# cpu_core.net
KiCad netlist of a schematic drawn in Altium Designer
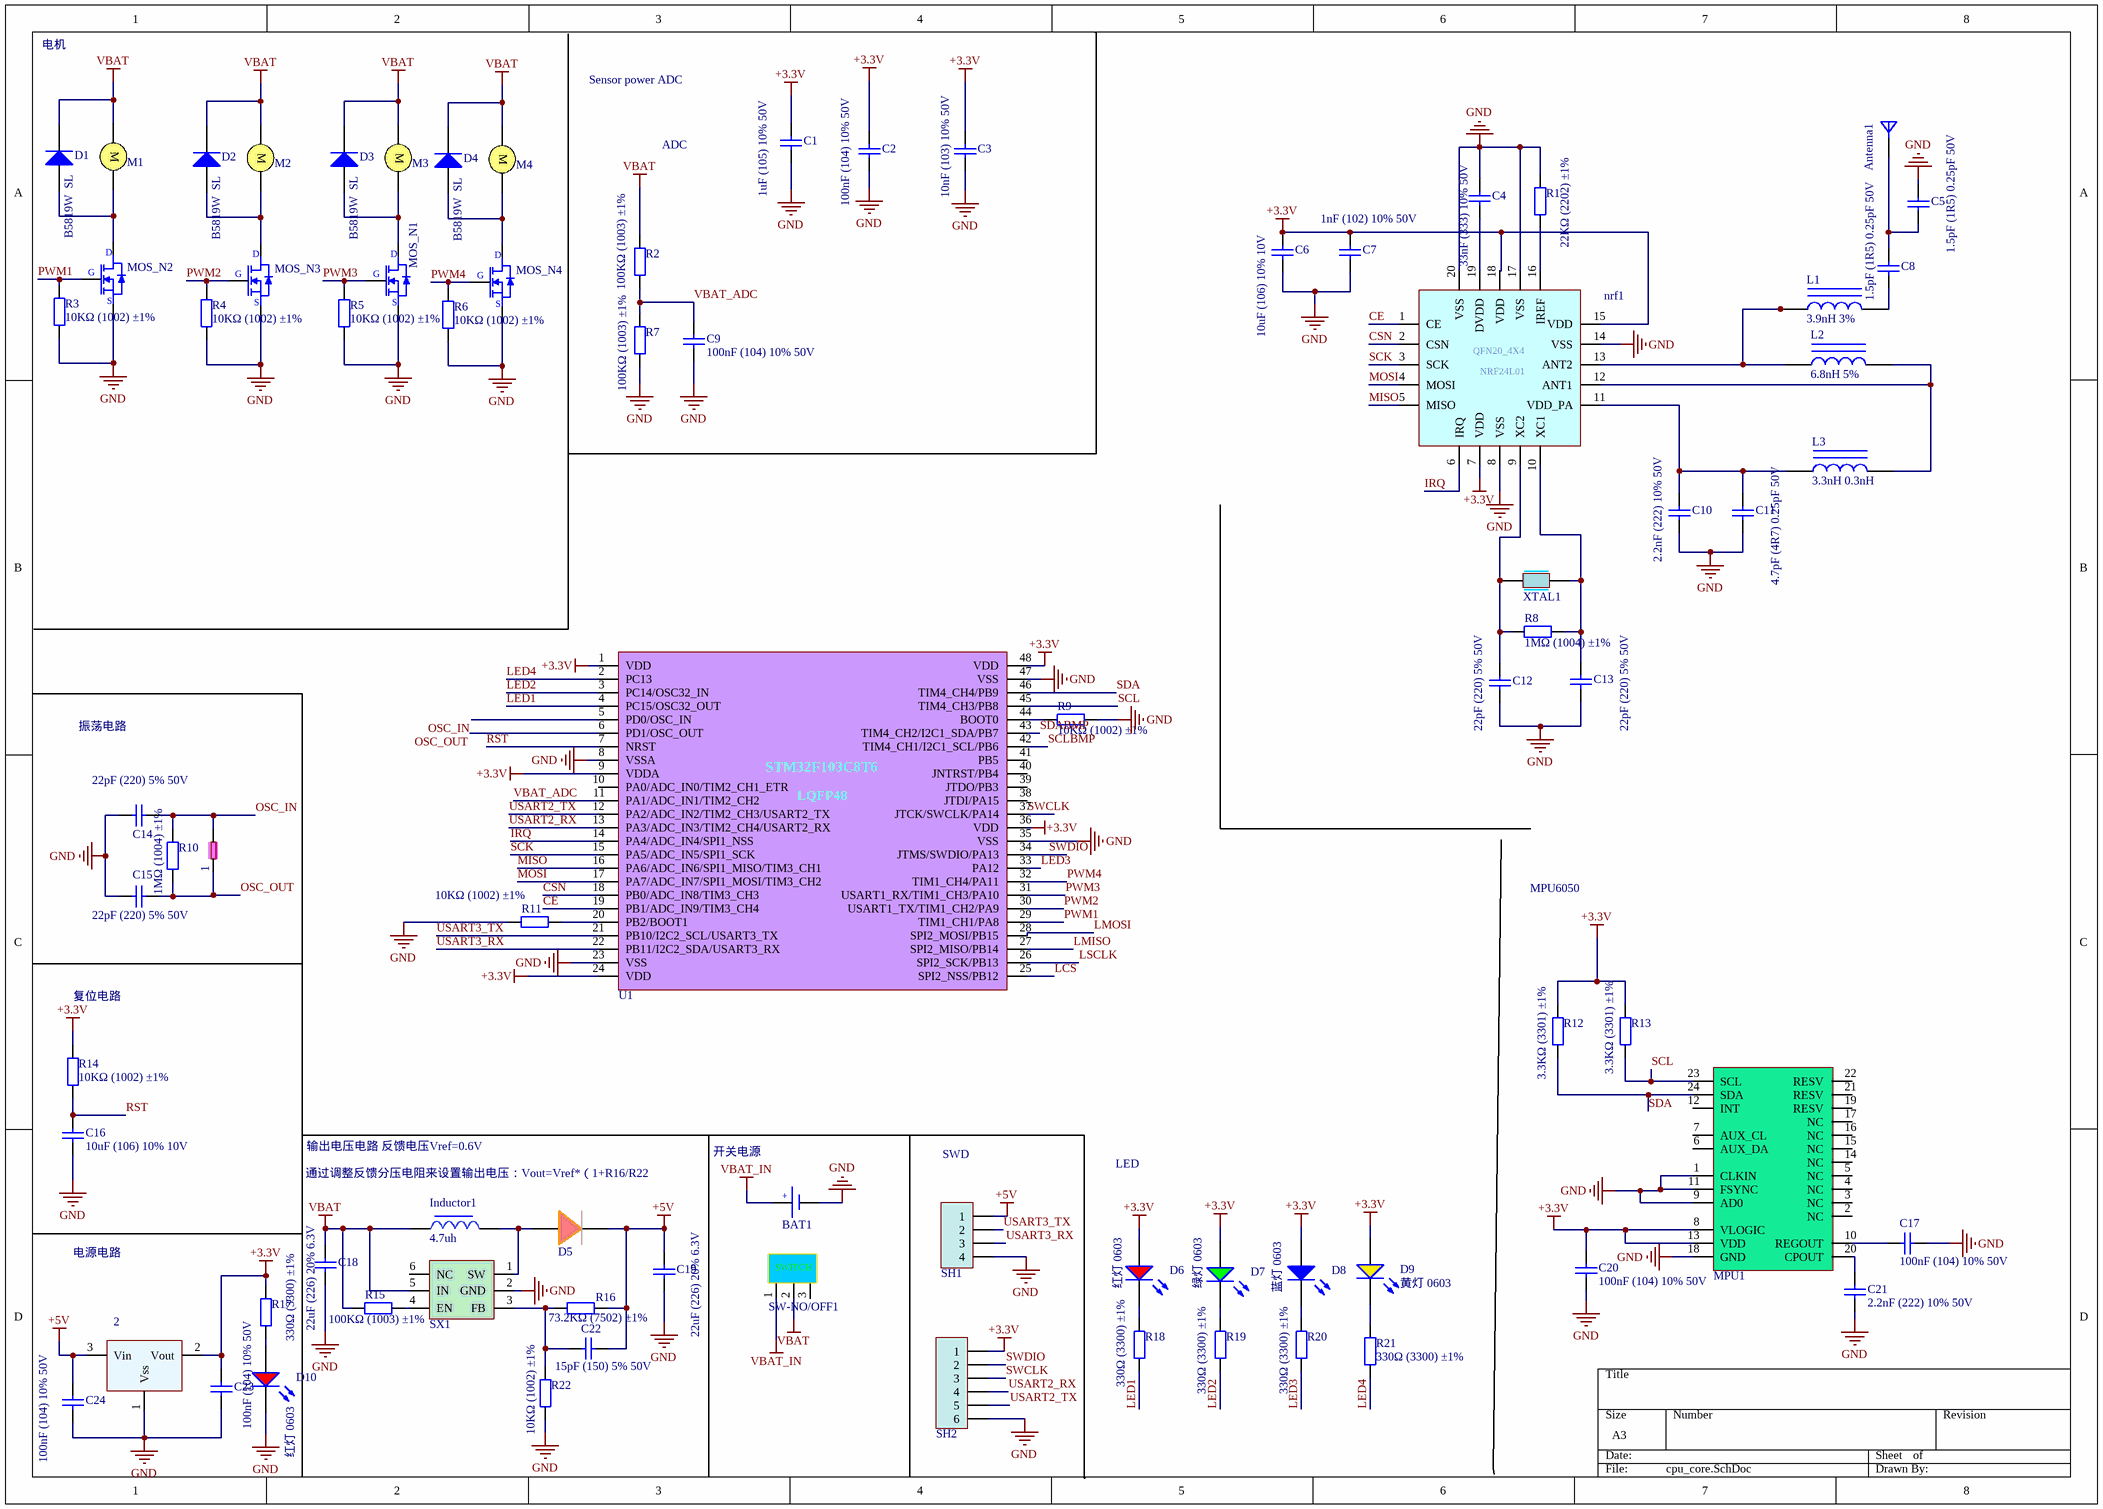
[diagram p0: cpu_core.SchDoc]

(export (version "E")
  (design (tool "Eeschema 10.0.6"))
  (components
    (comp (ref "1")
      (value "5032-8MHZ")
      (footprint "5032-8MHZ")
      (libsource (lib "self_schlib v1.8.6") (part "5032-8MHZ"))
    )
    (comp (ref "2")
      (value "662K-3.3V(SOT-23-3)")
      (footprint "SOT-23-3")
      (libsource (lib "self_schlib v1.8.6") (part "662K-3.3V(SOT-23-3)"))
    )
    (comp (ref "Antenna1")
      (value "Antenna")
      (footprint "Antenna")
      (libsource (lib "self_schlib v1.8.6") (part "Antenna"))
    )
    (comp (ref "BAT1") (value "BAT") (footprint "BAT") (libsource (lib "self_schlib v1.8.6") (part "BAT")))
    (comp (ref "C1")
      (value "1uF (105) 10% 50V")
      (footprint "0603_C")
      (description "贴片电容")
      (libsource (lib "Miscellaneous Devices Legend") (part "0603 1uF (105) 10% 50V"))
    )
    (comp (ref "C2")
      (value "100nF (104) 10% 50V")
      (footprint "0603_C")
      (description "贴片电容")
      (libsource (lib "Miscellaneous Devices Legend") (part "0603 100nF (104) 10% 50V"))
    )
    (comp (ref "C3")
      (value "10nF (103) 10% 50V")
      (footprint "0603_C")
      (description "贴片电容")
      (libsource (lib "Miscellaneous Devices Legend") (part "0603 10nF (103) 10% 50V"))
    )
    (comp (ref "C4")
      (value "33nF (333) 10% 50V")
      (footprint "0603_C")
      (description "贴片电容")
      (libsource (lib "Miscellaneous Devices Legend") (part "0603 33nF (333) 10% 50V"))
    )
    (comp (ref "C5")
      (value "1.5pF (1R5) 0.25pF 50V")
      (footprint "0402_C")
      (description "贴片电容")
      (libsource (lib "Miscellaneous Devices Legend") (part "0402 1.5pF (1R5) 0.25pF 50V"))
    )
    (comp (ref "C6")
      (value "10uF (106) 10% 10V")
      (footprint "0603_C")
      (description "贴片电容")
      (libsource (lib "Miscellaneous Devices Legend") (part "0603 10uF (106) 10% 10V"))
    )
    (comp (ref "C7")
      (value "1nF (102) 10% 50V")
      (footprint "0603_C")
      (description "贴片电容")
      (libsource (lib "Miscellaneous Devices Legend") (part "0603 1nF (102) 10% 50V"))
    )
    (comp (ref "C8")
      (value "1.5pF (1R5) 0.25pF 50V")
      (footprint "0402_C")
      (description "贴片电容")
      (libsource (lib "Miscellaneous Devices Legend") (part "0402 1.5pF (1R5) 0.25pF 50V"))
    )
    (comp (ref "C9")
      (value "100nF (104) 10% 50V")
      (footprint "0603_C")
      (description "贴片电容")
      (libsource (lib "Miscellaneous Devices Legend") (part "0603 100nF (104) 10% 50V"))
    )
    (comp (ref "C10")
      (value "2.2nF (222) 10% 50V")
      (footprint "0603_C")
      (description "贴片电容")
      (libsource (lib "Miscellaneous Devices Legend") (part "0603 2.2nF (222) 10% 50V"))
    )
    (comp (ref "C11")
      (value "4.7pF (4R7) 0.25pF 50V")
      (footprint "0603_C")
      (description "贴片电容")
      (libsource (lib "Miscellaneous Devices Legend") (part "0603 4.7pF (4R7) 0.25pF 50V"))
    )
    (comp (ref "C12")
      (value "22pF (220) 5% 50V")
      (footprint "0603_C")
      (description "贴片电容")
      (libsource (lib "Miscellaneous Devices Legend") (part "0603 22pF (220) 5% 50V"))
    )
    (comp (ref "C13")
      (value "22pF (220) 5% 50V")
      (footprint "0603_C")
      (description "贴片电容")
      (libsource (lib "Miscellaneous Devices Legend") (part "0603 22pF (220) 5% 50V"))
    )
    (comp (ref "C14")
      (value "22pF (220) 5% 50V")
      (footprint "0603_C")
      (description "贴片电容")
      (libsource (lib "Miscellaneous Devices Legend") (part "0603 22pF (220) 5% 50V"))
    )
    (comp (ref "C15")
      (value "22pF (220) 5% 50V")
      (footprint "0603_C")
      (description "贴片电容")
      (libsource (lib "Miscellaneous Devices Legend") (part "0603 22pF (220) 5% 50V"))
    )
    (comp (ref "C16")
      (value "10uF (106) 10% 10V")
      (footprint "0603_C")
      (description "贴片电容")
      (libsource (lib "Miscellaneous Devices Legend") (part "0603 10uF (106) 10% 10V"))
    )
    (comp (ref "C17")
      (value "100nF (104) 10% 50V")
      (footprint "0603_C")
      (description "贴片电容")
      (libsource (lib "Miscellaneous Devices Legend") (part "0603 100nF (104) 10% 50V"))
    )
    (comp (ref "C18")
      (value "22uF (226) 20% 6.3V")
      (footprint "0603_C")
      (description "贴片电容")
      (libsource (lib "Miscellaneous Devices Legend") (part "0603 22uF (226) 20% 6.3V"))
    )
    (comp (ref "C19")
      (value "22uF (226) 20% 6.3V")
      (footprint "0603_C")
      (description "贴片电容")
      (libsource (lib "Miscellaneous Devices Legend") (part "0603 22uF (226) 20% 6.3V"))
    )
    (comp (ref "C20")
      (value "100nF (104) 10% 50V")
      (footprint "0603_C")
      (description "贴片电容")
      (libsource (lib "Miscellaneous Devices Legend") (part "0603 100nF (104) 10% 50V"))
    )
    (comp (ref "C21")
      (value "2.2nF (222) 10% 50V")
      (footprint "0603_C")
      (description "贴片电容")
      (libsource (lib "Miscellaneous Devices Legend") (part "0603 2.2nF (222) 10% 50V"))
    )
    (comp (ref "C22")
      (value "15pF (150) 5% 50V")
      (footprint "0603_C")
      (description "贴片电容")
      (libsource (lib "Miscellaneous Devices Legend") (part "0603 15pF (150) 5% 50V"))
    )
    (comp (ref "C23")
      (value "100nF (104) 10% 50V")
      (footprint "0603_C")
      (description "贴片电容")
      (libsource (lib "Miscellaneous Devices Legend") (part "0603 100nF (104) 10% 50V"))
    )
    (comp (ref "C24")
      (value "100nF (104) 10% 50V")
      (footprint "0603_C")
      (description "贴片电容")
      (libsource (lib "Miscellaneous Devices Legend") (part "0603 100nF (104) 10% 50V"))
    )
    (comp (ref "D1")
      (value "B5819W  SL")
      (footprint "SOD-123")
      (description "肖特基二极管")
      (libsource (lib "Miscellaneous Devices Legend") (part "SOD-123 B5819W  SL"))
    )
    (comp (ref "D2")
      (value "B5819W  SL")
      (footprint "SOD-123")
      (description "肖特基二极管")
      (libsource (lib "Miscellaneous Devices Legend") (part "SOD-123 B5819W  SL"))
    )
    (comp (ref "D3")
      (value "B5819W  SL")
      (footprint "SOD-123")
      (description "肖特基二极管")
      (libsource (lib "Miscellaneous Devices Legend") (part "SOD-123 B5819W  SL"))
    )
    (comp (ref "D4")
      (value "B5819W  SL")
      (footprint "SOD-123")
      (description "肖特基二极管")
      (libsource (lib "Miscellaneous Devices Legend") (part "SOD-123 B5819W  SL"))
    )
    (comp (ref "D5")
      (value "SMA/DO-214")
      (footprint "SMA/DO-214")
      (libsource (lib "self_schlib v1.8.6") (part "SMA/DO-214"))
    )
    (comp (ref "D6")
      (value "红灯 0603")
      (footprint "0603_LED_S1")
      (description "发光二极管")
      (libsource (lib "Miscellaneous Devices Legend") (part "0603 红灯"))
    )
    (comp (ref "D7")
      (value "绿灯 0603")
      (footprint "0603_LED_S1")
      (description "发光二极管")
      (libsource (lib "Miscellaneous Devices Legend") (part "0603 绿灯"))
    )
    (comp (ref "D8")
      (value "蓝灯 0603")
      (footprint "0603_LED_S1")
      (description "发光二极管")
      (libsource (lib "Miscellaneous Devices Legend") (part "0603 蓝灯"))
    )
    (comp (ref "D9")
      (value "黄灯 0603")
      (footprint "0603_LED_S1")
      (description "发光二极管")
      (libsource (lib "Miscellaneous Devices Legend") (part "0603 黄灯"))
    )
    (comp (ref "D10")
      (value "红灯 0603")
      (footprint "0603_LED_S1")
      (description "发光二极管")
      (libsource (lib "Miscellaneous Devices Legend") (part "0603 红灯"))
    )
    (comp (ref "Inductor1")
      (value "Inductor")
      (footprint "CD32")
      (fields (field (name "ALTIUM_UNNAMED_1") "4.7uh"))
      (libsource (lib "self_schlib v1.8.6") (part "Inductor"))
    )
    (comp (ref "L1")
      (value "3.9nH 3%")
      (footprint "0402_L")
      (description "贴片电感")
      (libsource (lib "Miscellaneous Devices Legend") (part "0402 3.9nH 3%"))
    )
    (comp (ref "L2")
      (value "6.8nH 5%")
      (footprint "0402_L")
      (description "贴片电感")
      (libsource (lib "Miscellaneous Devices Legend") (part "0402 6.8nH 5%"))
    )
    (comp (ref "L3")
      (value "3.3nH 0.3nH")
      (footprint "0402_L")
      (description "贴片电感")
      (libsource (lib "Miscellaneous Devices Legend") (part "0402 3.3nH 0.3nH"))
    )
    (comp (ref "M1") (value "MOTO") (footprint "MOTO") (libsource (lib "self_schlib v1.8.6") (part "MOTO")))
    (comp (ref "M2") (value "MOTO") (footprint "MOTO") (libsource (lib "self_schlib v1.8.6") (part "MOTO")))
    (comp (ref "M3") (value "MOTO") (footprint "MOTO") (libsource (lib "self_schlib v1.8.6") (part "MOTO")))
    (comp (ref "M4") (value "MOTO") (footprint "MOTO") (libsource (lib "self_schlib v1.8.6") (part "MOTO")))
    (comp (ref "MOS_N1")
      (value "MOS_N")
      (footprint "SOT-23-3")
      (libsource (lib "self_schlib v1.8.6") (part "MOS_N_(SOT-23-3)"))
    )
    (comp (ref "MOS_N2")
      (value "MOS_N")
      (footprint "SOT-23-3")
      (libsource (lib "self_schlib v1.8.6") (part "MOS_N_(SOT-23-3)"))
    )
    (comp (ref "MOS_N3")
      (value "MOS_N")
      (footprint "SOT-23-3")
      (libsource (lib "self_schlib v1.8.6") (part "MOS_N_(SOT-23-3)"))
    )
    (comp (ref "MOS_N4")
      (value "MOS_N")
      (footprint "SOT-23-3")
      (libsource (lib "self_schlib v1.8.6") (part "MOS_N_(SOT-23-3)"))
    )
    (comp (ref "MPU1")
      (value "MPU6050")
      (footprint "QFN24_4X4")
      (libsource (lib "self_schlib v1.8.6") (part "MPU6050(QFN24_4X4)"))
    )
    (comp (ref "nrf1")
      (value "nrf24l01")
      (footprint "QFN20_4X4")
      (libsource (lib "self_schlib v1.8.6") (part "QFN20-4X4"))
    )
    (comp (ref "R1")
      (value "22KΩ (2202) ±1%")
      (footprint "0603_R")
      (description "贴片电阻")
      (libsource (lib "Miscellaneous Devices Legend") (part "0603 22KΩ (2202) 1%"))
    )
    (comp (ref "R2")
      (value "100KΩ (1003) ±1%")
      (footprint "0603_R")
      (description "贴片电阻")
      (libsource (lib "") (part "0603 100KΩ (1003) 1%_1"))
    )
    (comp (ref "R3")
      (value "10KΩ (1002) ±1%")
      (footprint "0603_R")
      (description "贴片电阻")
      (libsource (lib "Miscellaneous Devices Legend") (part "0603 10KΩ (1002) 1%"))
    )
    (comp (ref "R4")
      (value "10KΩ (1002) ±1%")
      (footprint "0603_R")
      (description "贴片电阻")
      (libsource (lib "Miscellaneous Devices Legend") (part "0603 10KΩ (1002) 1%"))
    )
    (comp (ref "R5")
      (value "10KΩ (1002) ±1%")
      (footprint "0603_R")
      (description "贴片电阻")
      (libsource (lib "Miscellaneous Devices Legend") (part "0603 10KΩ (1002) 1%"))
    )
    (comp (ref "R6")
      (value "10KΩ (1002) ±1%")
      (footprint "0603_R")
      (description "贴片电阻")
      (libsource (lib "Miscellaneous Devices Legend") (part "0603 10KΩ (1002) 1%"))
    )
    (comp (ref "R7")
      (value "100KΩ (1003) ±1%")
      (footprint "0603_R")
      (description "贴片电阻")
      (libsource (lib "") (part "0603 100KΩ (1003) 1%_1"))
    )
    (comp (ref "R8")
      (value "1MΩ (1004) ±1%")
      (footprint "0603_R")
      (description "贴片电阻")
      (libsource (lib "Miscellaneous Devices Legend") (part "0603 1MΩ (1004) 1%"))
    )
    (comp (ref "R9")
      (value "10KΩ (1002) ±1%")
      (footprint "0603_R")
      (description "贴片电阻")
      (libsource (lib "") (part "0603 10KΩ (1002) 1%_1"))
    )
    (comp (ref "R10")
      (value "1MΩ (1004) ±1%")
      (footprint "0603_R")
      (description "贴片电阻")
      (libsource (lib "") (part "0603 1MΩ (1004) 1%_1"))
    )
    (comp (ref "R11")
      (value "10KΩ (1002) ±1%")
      (footprint "0603_R")
      (description "贴片电阻")
      (libsource (lib "") (part "0603 10KΩ (1002) 1%_2"))
    )
    (comp (ref "R12")
      (value "3.3KΩ (3301) ±1%")
      (footprint "0603_R")
      (description "贴片电阻")
      (libsource (lib "Miscellaneous Devices Legend") (part "0603 3.3KΩ (3301) 1%"))
    )
    (comp (ref "R13")
      (value "3.3KΩ (3301) ±1%")
      (footprint "0603_R")
      (description "贴片电阻")
      (libsource (lib "Miscellaneous Devices Legend") (part "0603 3.3KΩ (3301) 1%"))
    )
    (comp (ref "R14")
      (value "10KΩ (1002) ±1%")
      (footprint "0603_R")
      (description "贴片电阻")
      (libsource (lib "Miscellaneous Devices Legend") (part "0603 10KΩ (1002) 1%"))
    )
    (comp (ref "R15")
      (value "100KΩ (1003) ±1%")
      (footprint "0603_R")
      (description "贴片电阻")
      (libsource (lib "Miscellaneous Devices Legend") (part "0603 100KΩ (1003) 1%"))
    )
    (comp (ref "R16")
      (value "73.2KΩ (7502) ±1%")
      (footprint "0603_R")
      (description "贴片电阻")
      (libsource (lib "Miscellaneous Devices Legend") (part "0603 75KΩ (7502) 1%"))
    )
    (comp (ref "R17")
      (value "330Ω (3300) ±1%")
      (footprint "0603_R")
      (description "贴片电阻")
      (libsource (lib "Miscellaneous Devices Legend") (part "0603 330Ω (3300) 1%"))
    )
    (comp (ref "R18")
      (value "330Ω (3300) ±1%")
      (footprint "0603_R")
      (description "贴片电阻")
      (libsource (lib "Miscellaneous Devices Legend") (part "0603 330Ω (3300) 1%"))
    )
    (comp (ref "R19")
      (value "330Ω (3300) ±1%")
      (footprint "0603_R")
      (description "贴片电阻")
      (libsource (lib "Miscellaneous Devices Legend") (part "0603 330Ω (3300) 1%"))
    )
    (comp (ref "R20")
      (value "330Ω (3300) ±1%")
      (footprint "0603_R")
      (description "贴片电阻")
      (libsource (lib "Miscellaneous Devices Legend") (part "0603 330Ω (3300) 1%"))
    )
    (comp (ref "R21")
      (value "330Ω (3300) ±1%")
      (footprint "0603_R")
      (description "贴片电阻")
      (libsource (lib "Miscellaneous Devices Legend") (part "0603 330Ω (3300) 1%"))
    )
    (comp (ref "R22")
      (value "10KΩ (1002) ±1%")
      (footprint "0603_R")
      (description "贴片电阻")
      (libsource (lib "Miscellaneous Devices Legend") (part "0603 10KΩ (1002) 1%"))
    )
    (comp (ref "SH1")
      (value "SH1.0mm-4PIN")
      (footprint "SH1.0mm-4PIN")
      (libsource (lib "self_schlib v1.8.6") (part "SH1.0mm-4PIN"))
    )
    (comp (ref "SH2")
      (value "SH1.0mm-6PIN")
      (footprint "SH1.0mm-6PIN")
      (libsource (lib "self_schlib v1.8.6") (part "SH1.0mm-6PIN"))
    )
    (comp (ref "SW-NO/OFF1")
      (value "SW-NO/OFF")
      (footprint "SW-NO/OFF-PIN3")
      (libsource (lib "self_schlib v1.8.6") (part "SW-NO/OFF-PIN3"))
    )
    (comp (ref "SX1")
      (value "SX1308")
      (footprint "SX1308")
      (libsource (lib "self_schlib v1.8.6") (part "SX1308"))
    )
    (comp (ref "U1")
      (value "STM32F103C8T6")
      (footprint "STM32F103C8T6")
      (libsource (lib "self_schlib v1.8.6") (part "STM32F103C8T6"))
    )
    (comp (ref "XTAL1")
      (value "Crystal Oscillator 3225")
      (footprint "Crystal Oscillator 3225")
      (libsource (lib "self_schlib v1.8.6") (part "Crystal Oscillator 3225"))
    )
  )
  (nets
    (net (code "1") (name "+3.3V") (class "Default")
      (node (ref "2") (pin "2") (pinfunction "Vout_2") (pintype "passive"))
      (node (ref "C1") (pin "2") (pinfunction "2_2") (pintype "passive"))
      (node (ref "C2") (pin "2") (pinfunction "2_2") (pintype "passive"))
      (node (ref "C20") (pin "2") (pinfunction "2_2") (pintype "passive"))
      (node (ref "C23") (pin "2") (pinfunction "2_2") (pintype "passive"))
      (node (ref "C3") (pin "2") (pinfunction "2_2") (pintype "passive"))
      (node (ref "C6") (pin "2") (pinfunction "2_2") (pintype "passive"))
      (node (ref "C7") (pin "2") (pinfunction "2_2") (pintype "passive"))
      (node (ref "D6") (pin "A") (pinfunction "A_A") (pintype "passive"))
      (node (ref "D7") (pin "A") (pinfunction "A_A") (pintype "passive"))
      (node (ref "D8") (pin "A") (pinfunction "A_A") (pintype "passive"))
      (node (ref "D9") (pin "A") (pinfunction "A_A") (pintype "passive"))
      (node (ref "MPU1") (pin "13") (pinfunction "VDD_13") (pintype "passive"))
      (node (ref "MPU1") (pin "8") (pinfunction "VLOGIC_8") (pintype "passive"))
      (node (ref "R12") (pin "2") (pinfunction "2_2") (pintype "passive"))
      (node (ref "R13") (pin "2") (pinfunction "2_2") (pintype "passive"))
      (node (ref "R14") (pin "2") (pinfunction "2_2") (pintype "passive"))
      (node (ref "R17") (pin "2") (pinfunction "2_2") (pintype "passive"))
      (node (ref "SH2") (pin "1") (pinfunction "1_1") (pintype "passive"))
      (node (ref "U1") (pin "1") (pinfunction "VDD_1") (pintype "passive"))
      (node (ref "U1") (pin "24") (pinfunction "VDD_24") (pintype "passive"))
      (node (ref "U1") (pin "36") (pinfunction "VDD_36") (pintype "passive"))
      (node (ref "U1") (pin "48") (pinfunction "VDD_48") (pintype "passive"))
      (node (ref "U1") (pin "9") (pinfunction "VDDA_9") (pintype "passive"))
      (node (ref "nrf1") (pin "15") (pinfunction "VDD_15") (pintype "passive"))
      (node (ref "nrf1") (pin "7") (pinfunction "VDD_7") (pintype "passive"))
    )
    (net (code "2") (name "+5V") (class "Default")
      (node (ref "2") (pin "3") (pinfunction "Vin_3") (pintype "passive"))
      (node (ref "C19") (pin "2") (pinfunction "2_2") (pintype "passive"))
      (node (ref "C22") (pin "2") (pinfunction "2_2") (pintype "passive"))
      (node (ref "C24") (pin "2") (pinfunction "2_2") (pintype "passive"))
      (node (ref "D5") (pin "2") (pinfunction "2_2") (pintype "passive"))
      (node (ref "R16") (pin "2") (pinfunction "2_2") (pintype "passive"))
      (node (ref "SH1") (pin "1") (pinfunction "1_1") (pintype "passive"))
    )
    (net (code "3") (name "/CE") (class "Default")
      (node (ref "U1") (pin "19") (pinfunction "PB1/ADC_IN9/TIM3_CH4_19") (pintype "passive"))
      (node (ref "nrf1") (pin "1") (pinfunction "CE_1") (pintype "passive"))
    )
    (net (code "4") (name "/CSN") (class "Default")
      (node (ref "U1") (pin "18") (pinfunction "PB0/ADC_IN8/TIM3_CH3_18") (pintype "passive"))
      (node (ref "nrf1") (pin "2") (pinfunction "CSN_2") (pintype "passive"))
    )
    (net (code "5") (name "/IRQ") (class "Default")
      (node (ref "U1") (pin "14") (pinfunction "PA4/ADC_IN4/SPI1_NSS_14") (pintype "passive"))
      (node (ref "nrf1") (pin "6") (pinfunction "IRQ_6") (pintype "passive"))
    )
    (net (code "6") (name "/LCS") (class "Default")
      (node (ref "U1") (pin "25") (pinfunction "SPI2_NSS/PB12_25") (pintype "passive"))
    )
    (net (code "7") (name "/LED1") (class "Default")
      (node (ref "R18") (pin "1") (pinfunction "1_1") (pintype "passive"))
      (node (ref "U1") (pin "4") (pinfunction "PC15/OSC32_OUT_4") (pintype "passive"))
    )
    (net (code "8") (name "/LED2") (class "Default")
      (node (ref "R19") (pin "1") (pinfunction "1_1") (pintype "passive"))
      (node (ref "U1") (pin "3") (pinfunction "PC14/OSC32_IN_3") (pintype "passive"))
    )
    (net (code "9") (name "/LED3") (class "Default")
      (node (ref "R20") (pin "1") (pinfunction "1_1") (pintype "passive"))
      (node (ref "U1") (pin "33") (pinfunction "PA12_33") (pintype "passive"))
    )
    (net (code "10") (name "/LED4") (class "Default")
      (node (ref "R21") (pin "1") (pinfunction "1_1") (pintype "passive"))
      (node (ref "U1") (pin "2") (pinfunction "PC13_2") (pintype "passive"))
    )
    (net (code "11") (name "/LMISO") (class "Default")
      (node (ref "U1") (pin "27") (pinfunction "SPI2_MISO/PB14_27") (pintype "passive"))
    )
    (net (code "12") (name "/LMOSI") (class "Default")
      (node (ref "U1") (pin "28") (pinfunction "SPI2_MOSI/PB15_28") (pintype "passive"))
    )
    (net (code "13") (name "/LSCLK") (class "Default")
      (node (ref "U1") (pin "26") (pinfunction "SPI2_SCK/PB13_26") (pintype "passive"))
    )
    (net (code "14") (name "/MISO") (class "Default")
      (node (ref "U1") (pin "16") (pinfunction "PA6/ADC_IN6/SPI1_MISO/TIM3_CH1_16") (pintype "passive"))
      (node (ref "nrf1") (pin "5") (pinfunction "MISO_5") (pintype "passive"))
    )
    (net (code "15") (name "/MOSI") (class "Default")
      (node (ref "U1") (pin "17") (pinfunction "PA7/ADC_IN7/SPI1_MOSI/TIM3_CH2_17") (pintype "passive"))
      (node (ref "nrf1") (pin "4") (pinfunction "MOSI_4") (pintype "passive"))
    )
    (net (code "16") (name "/OSC_IN") (class "Default")
      (node (ref "1") (pin "3") (pinfunction "3_3") (pintype "passive"))
      (node (ref "C14") (pin "2") (pinfunction "2_2") (pintype "passive"))
      (node (ref "R10") (pin "2") (pinfunction "2_2") (pintype "passive"))
      (node (ref "U1") (pin "5") (pinfunction "PD0/OSC_IN_5") (pintype "passive"))
    )
    (net (code "17") (name "/OSC_OUT") (class "Default")
      (node (ref "1") (pin "1") (pinfunction "1_1") (pintype "passive"))
      (node (ref "C15") (pin "2") (pinfunction "2_2") (pintype "passive"))
      (node (ref "R10") (pin "1") (pinfunction "1_1") (pintype "passive"))
      (node (ref "U1") (pin "6") (pinfunction "PD1/OSC_OUT_6") (pintype "passive"))
    )
    (net (code "18") (name "/PWM1") (class "Default")
      (node (ref "MOS_N2") (pin "1") (pinfunction "G_1") (pintype "passive"))
      (node (ref "R3") (pin "2") (pinfunction "2_2") (pintype "passive"))
      (node (ref "U1") (pin "29") (pinfunction "TIM1_CH1/PA8_29") (pintype "passive"))
    )
    (net (code "19") (name "/PWM2") (class "Default")
      (node (ref "MOS_N3") (pin "1") (pinfunction "G_1") (pintype "passive"))
      (node (ref "R4") (pin "2") (pinfunction "2_2") (pintype "passive"))
      (node (ref "U1") (pin "30") (pinfunction "USART1_TX/TIM1_CH2/PA9_30") (pintype "passive"))
    )
    (net (code "20") (name "/PWM3") (class "Default")
      (node (ref "MOS_N1") (pin "1") (pinfunction "G_1") (pintype "passive"))
      (node (ref "R5") (pin "2") (pinfunction "2_2") (pintype "passive"))
      (node (ref "U1") (pin "31") (pinfunction "USART1_RX/TIM1_CH3/PA10_31") (pintype "passive"))
    )
    (net (code "21") (name "/PWM4") (class "Default")
      (node (ref "MOS_N4") (pin "1") (pinfunction "G_1") (pintype "passive"))
      (node (ref "R6") (pin "2") (pinfunction "2_2") (pintype "passive"))
      (node (ref "U1") (pin "32") (pinfunction "TIM1_CH4/PA11_32") (pintype "passive"))
    )
    (net (code "22") (name "/RST") (class "Default")
      (node (ref "C16") (pin "2") (pinfunction "2_2") (pintype "passive"))
      (node (ref "R14") (pin "1") (pinfunction "1_1") (pintype "passive"))
      (node (ref "U1") (pin "7") (pinfunction "NRST_7") (pintype "passive"))
    )
    (net (code "23") (name "/SCK") (class "Default")
      (node (ref "U1") (pin "15") (pinfunction "PA5/ADC_IN5/SPI1_SCK_15") (pintype "passive"))
      (node (ref "nrf1") (pin "3") (pinfunction "SCK_3") (pintype "passive"))
    )
    (net (code "24") (name "/SCL") (class "Default")
      (node (ref "MPU1") (pin "23") (pinfunction "SCL_23") (pintype "passive"))
      (node (ref "R13") (pin "1") (pinfunction "1_1") (pintype "passive"))
      (node (ref "U1") (pin "45") (pinfunction "TIM4_CH3/PB8_45") (pintype "passive"))
    )
    (net (code "25") (name "/SCLBMP") (class "Default")
      (node (ref "U1") (pin "42") (pinfunction "TIM4_CH1/I2C1_SCL/PB6_42") (pintype "passive"))
    )
    (net (code "26") (name "/SDA") (class "Default")
      (node (ref "MPU1") (pin "24") (pinfunction "SDA_24") (pintype "passive"))
      (node (ref "R12") (pin "1") (pinfunction "1_1") (pintype "passive"))
      (node (ref "U1") (pin "46") (pinfunction "TIM4_CH4/PB9_46") (pintype "passive"))
    )
    (net (code "27") (name "/SDABMP") (class "Default")
      (node (ref "U1") (pin "43") (pinfunction "TIM4_CH2/I2C1_SDA/PB7_43") (pintype "passive"))
    )
    (net (code "28") (name "/SWCLK") (class "Default")
      (node (ref "SH2") (pin "3") (pinfunction "3_3") (pintype "passive"))
      (node (ref "U1") (pin "37") (pinfunction "JTCK/SWCLK/PA14_37") (pintype "passive"))
    )
    (net (code "29") (name "/SWDIO") (class "Default")
      (node (ref "SH2") (pin "2") (pinfunction "2_2") (pintype "passive"))
      (node (ref "U1") (pin "34") (pinfunction "JTMS/SWDIO/PA13_34") (pintype "passive"))
    )
    (net (code "30") (name "/USART2_RX") (class "Default")
      (node (ref "SH2") (pin "4") (pinfunction "4_4") (pintype "passive"))
      (node (ref "U1") (pin "13") (pinfunction "PA3/ADC_IN3/TIM2_CH4/USART2_RX_13") (pintype "passive"))
    )
    (net (code "31") (name "/USART2_TX") (class "Default")
      (node (ref "SH2") (pin "5") (pinfunction "5_5") (pintype "passive"))
      (node (ref "U1") (pin "12") (pinfunction "PA2/ADC_IN2/TIM2_CH3/USART2_TX_12") (pintype "passive"))
    )
    (net (code "32") (name "/USART3_RX") (class "Default")
      (node (ref "SH1") (pin "3") (pinfunction "3_3") (pintype "passive"))
      (node (ref "U1") (pin "22") (pinfunction "PB11/I2C2_SDA/USART3_RX_22") (pintype "passive"))
    )
    (net (code "33") (name "/USART3_TX") (class "Default")
      (node (ref "SH1") (pin "2") (pinfunction "2_2") (pintype "passive"))
      (node (ref "U1") (pin "21") (pinfunction "PB10/I2C2_SCL/USART3_TX_21") (pintype "passive"))
    )
    (net (code "34") (name "/VBAT_ADC") (class "Default")
      (node (ref "C9") (pin "2") (pinfunction "2_2") (pintype "passive"))
      (node (ref "R2") (pin "1") (pinfunction "1_1") (pintype "passive"))
      (node (ref "R7") (pin "2") (pinfunction "2_2") (pintype "passive"))
      (node (ref "U1") (pin "11") (pinfunction "PA1/ADC_IN1/TIM2_CH2_11") (pintype "passive"))
    )
    (net (code "35") (name "GND") (class "Default")
      (node (ref "2") (pin "1") (pinfunction "Vss_1") (pintype "passive"))
      (node (ref "BAT1") (pin "2") (pinfunction "-_2") (pintype "passive"))
      (node (ref "C1") (pin "1") (pinfunction "1_1") (pintype "passive"))
      (node (ref "C10") (pin "1") (pinfunction "1_1") (pintype "passive"))
      (node (ref "C11") (pin "1") (pinfunction "1_1") (pintype "passive"))
      (node (ref "C12") (pin "1") (pinfunction "1_1") (pintype "passive"))
      (node (ref "C13") (pin "1") (pinfunction "1_1") (pintype "passive"))
      (node (ref "C14") (pin "1") (pinfunction "1_1") (pintype "passive"))
      (node (ref "C15") (pin "1") (pinfunction "1_1") (pintype "passive"))
      (node (ref "C16") (pin "1") (pinfunction "1_1") (pintype "passive"))
      (node (ref "C17") (pin "2") (pinfunction "2_2") (pintype "passive"))
      (node (ref "C18") (pin "1") (pinfunction "1_1") (pintype "passive"))
      (node (ref "C19") (pin "1") (pinfunction "1_1") (pintype "passive"))
      (node (ref "C2") (pin "1") (pinfunction "1_1") (pintype "passive"))
      (node (ref "C20") (pin "1") (pinfunction "1_1") (pintype "passive"))
      (node (ref "C21") (pin "1") (pinfunction "1_1") (pintype "passive"))
      (node (ref "C23") (pin "1") (pinfunction "1_1") (pintype "passive"))
      (node (ref "C24") (pin "1") (pinfunction "1_1") (pintype "passive"))
      (node (ref "C3") (pin "1") (pinfunction "1_1") (pintype "passive"))
      (node (ref "C4") (pin "2") (pinfunction "2_2") (pintype "passive"))
      (node (ref "C5") (pin "2") (pinfunction "2_2") (pintype "passive"))
      (node (ref "C6") (pin "1") (pinfunction "1_1") (pintype "passive"))
      (node (ref "C7") (pin "1") (pinfunction "1_1") (pintype "passive"))
      (node (ref "C9") (pin "1") (pinfunction "1_1") (pintype "passive"))
      (node (ref "D10") (pin "K") (pinfunction "K_K") (pintype "passive"))
      (node (ref "MOS_N1") (pin "2") (pinfunction "S_2") (pintype "passive"))
      (node (ref "MOS_N2") (pin "2") (pinfunction "S_2") (pintype "passive"))
      (node (ref "MOS_N3") (pin "2") (pinfunction "S_2") (pintype "passive"))
      (node (ref "MOS_N4") (pin "2") (pinfunction "S_2") (pintype "passive"))
      (node (ref "MPU1") (pin "1") (pinfunction "CLKIN_1") (pintype "passive"))
      (node (ref "MPU1") (pin "11") (pinfunction "FSYNC_11") (pintype "passive"))
      (node (ref "MPU1") (pin "18") (pinfunction "GND_18") (pintype "passive"))
      (node (ref "MPU1") (pin "9") (pinfunction "AD0_9") (pintype "passive"))
      (node (ref "R1") (pin "2") (pinfunction "2_2") (pintype "passive"))
      (node (ref "R11") (pin "2") (pinfunction "2_2") (pintype "passive"))
      (node (ref "R22") (pin "1") (pinfunction "1_1") (pintype "passive"))
      (node (ref "R3") (pin "1") (pinfunction "1_1") (pintype "passive"))
      (node (ref "R4") (pin "1") (pinfunction "1_1") (pintype "passive"))
      (node (ref "R5") (pin "1") (pinfunction "1_1") (pintype "passive"))
      (node (ref "R6") (pin "1") (pinfunction "1_1") (pintype "passive"))
      (node (ref "R7") (pin "1") (pinfunction "1_1") (pintype "passive"))
      (node (ref "R9") (pin "2") (pinfunction "2_2") (pintype "passive"))
      (node (ref "SH1") (pin "4") (pinfunction "4_4") (pintype "passive"))
      (node (ref "SH2") (pin "6") (pinfunction "6_6") (pintype "passive"))
      (node (ref "SX1") (pin "2") (pinfunction "GND_2") (pintype "passive"))
      (node (ref "U1") (pin "23") (pinfunction "VSS_23") (pintype "passive"))
      (node (ref "U1") (pin "35") (pinfunction "VSS_35") (pintype "passive"))
      (node (ref "U1") (pin "47") (pinfunction "VSS_47") (pintype "passive"))
      (node (ref "U1") (pin "8") (pinfunction "VSSA_8") (pintype "passive"))
      (node (ref "nrf1") (pin "14") (pinfunction "VSS_14") (pintype "passive"))
      (node (ref "nrf1") (pin "17") (pinfunction "VSS_17") (pintype "passive"))
      (node (ref "nrf1") (pin "20") (pinfunction "VSS_20") (pintype "passive"))
      (node (ref "nrf1") (pin "8") (pinfunction "VSS_8") (pintype "passive"))
    )
    (net (code "36") (name "Net-(Antenna1-Pad1)") (class "Default")
      (node (ref "Antenna1") (pin "1") (pinfunction "1_1") (pintype "passive"))
      (node (ref "C5") (pin "1") (pinfunction "1_1") (pintype "passive"))
      (node (ref "C8") (pin "2") (pinfunction "2_2") (pintype "passive"))
    )
    (net (code "37") (name "Net-(C8-Pad1)") (class "Default")
      (node (ref "C8") (pin "1") (pinfunction "1_1") (pintype "passive"))
      (node (ref "L1") (pin "2") (pinfunction "2_2") (pintype "passive"))
    )
    (net (code "38") (name "Net-(D1-A)") (class "Default")
      (node (ref "D1") (pin "1") (pinfunction "A_1") (pintype "passive"))
      (node (ref "M1") (pin "2") (pinfunction "2_2") (pintype "tri_state"))
      (node (ref "MOS_N2") (pin "3") (pinfunction "D_3") (pintype "passive"))
    )
    (net (code "39") (name "Net-(D2-A)") (class "Default")
      (node (ref "D2") (pin "1") (pinfunction "A_1") (pintype "passive"))
      (node (ref "M2") (pin "2") (pinfunction "2_2") (pintype "tri_state"))
      (node (ref "MOS_N3") (pin "3") (pinfunction "D_3") (pintype "passive"))
    )
    (net (code "40") (name "Net-(D3-A)") (class "Default")
      (node (ref "D3") (pin "1") (pinfunction "A_1") (pintype "passive"))
      (node (ref "M3") (pin "2") (pinfunction "2_2") (pintype "tri_state"))
      (node (ref "MOS_N1") (pin "3") (pinfunction "D_3") (pintype "passive"))
    )
    (net (code "41") (name "Net-(D4-A)") (class "Default")
      (node (ref "D4") (pin "1") (pinfunction "A_1") (pintype "passive"))
      (node (ref "M4") (pin "2") (pinfunction "2_2") (pintype "tri_state"))
      (node (ref "MOS_N4") (pin "3") (pinfunction "D_3") (pintype "passive"))
    )
    (net (code "42") (name "Net-(D6-PadK)") (class "Default")
      (node (ref "D6") (pin "K") (pinfunction "K_K") (pintype "passive"))
      (node (ref "R18") (pin "2") (pinfunction "2_2") (pintype "passive"))
    )
    (net (code "43") (name "Net-(D7-PadK)") (class "Default")
      (node (ref "D7") (pin "K") (pinfunction "K_K") (pintype "passive"))
      (node (ref "R19") (pin "2") (pinfunction "2_2") (pintype "passive"))
    )
    (net (code "44") (name "Net-(D8-PadK)") (class "Default")
      (node (ref "D8") (pin "K") (pinfunction "K_K") (pintype "passive"))
      (node (ref "R20") (pin "2") (pinfunction "2_2") (pintype "passive"))
    )
    (net (code "45") (name "Net-(D9-PadK)") (class "Default")
      (node (ref "D9") (pin "K") (pinfunction "K_K") (pintype "passive"))
      (node (ref "R21") (pin "2") (pinfunction "2_2") (pintype "passive"))
    )
    (net (code "46") (name "Net-(D10-PadA)") (class "Default")
      (node (ref "D10") (pin "A") (pinfunction "A_A") (pintype "passive"))
      (node (ref "R17") (pin "1") (pinfunction "1_1") (pintype "passive"))
    )
    (net (code "47") (name "Net-(MPU1-CPOUT)") (class "Default")
      (node (ref "C21") (pin "2") (pinfunction "2_2") (pintype "passive"))
      (node (ref "MPU1") (pin "20") (pinfunction "CPOUT_20") (pintype "passive"))
    )
    (net (code "48") (name "Net-(MPU1-REGOUT)") (class "Default")
      (node (ref "C17") (pin "1") (pinfunction "1_1") (pintype "passive"))
      (node (ref "MPU1") (pin "10") (pinfunction "REGOUT_10") (pintype "passive"))
    )
    (net (code "49") (name "Net-(SX1-EN)") (class "Default")
      (node (ref "R15") (pin "2") (pinfunction "2_2") (pintype "passive"))
      (node (ref "SX1") (pin "4") (pinfunction "EN_4") (pintype "passive"))
    )
    (net (code "50") (name "Net-(SX1-FB)") (class "Default")
      (node (ref "C22") (pin "1") (pinfunction "1_1") (pintype "passive"))
      (node (ref "R16") (pin "1") (pinfunction "1_1") (pintype "passive"))
      (node (ref "R22") (pin "2") (pinfunction "2_2") (pintype "passive"))
      (node (ref "SX1") (pin "3") (pinfunction "FB_3") (pintype "passive"))
    )
    (net (code "51") (name "Net-(SX1-SW)") (class "Default")
      (node (ref "D5") (pin "1") (pinfunction "1_1") (pintype "passive"))
      (node (ref "Inductor1") (pin "2") (pinfunction "2_2") (pintype "passive"))
      (node (ref "SX1") (pin "1") (pinfunction "SW_1") (pintype "passive"))
    )
    (net (code "52") (name "Net-(U1-BOOT0)") (class "Default")
      (node (ref "R9") (pin "1") (pinfunction "1_1") (pintype "passive"))
      (node (ref "U1") (pin "44") (pinfunction "BOOT0_44") (pintype "passive"))
    )
    (net (code "53") (name "Net-(U1-PB2{slash}BOOT1)") (class "Default")
      (node (ref "R11") (pin "1") (pinfunction "1_1") (pintype "passive"))
      (node (ref "U1") (pin "20") (pinfunction "PB2/BOOT1_20") (pintype "passive"))
    )
    (net (code "54") (name "Net-(nrf1-ANT1)") (class "Default")
      (node (ref "L2") (pin "2") (pinfunction "2_2") (pintype "passive"))
      (node (ref "L3") (pin "2") (pinfunction "2_2") (pintype "passive"))
      (node (ref "nrf1") (pin "12") (pinfunction "ANT1_12") (pintype "passive"))
    )
    (net (code "55") (name "Net-(nrf1-ANT2)") (class "Default")
      (node (ref "L1") (pin "1") (pinfunction "1_1") (pintype "passive"))
      (node (ref "L2") (pin "1") (pinfunction "1_1") (pintype "passive"))
      (node (ref "nrf1") (pin "13") (pinfunction "ANT2_13") (pintype "passive"))
    )
    (net (code "56") (name "Net-(nrf1-DVDD)") (class "Default")
      (node (ref "C4") (pin "1") (pinfunction "1_1") (pintype "passive"))
      (node (ref "nrf1") (pin "19") (pinfunction "DVDD_19") (pintype "passive"))
    )
    (net (code "57") (name "Net-(nrf1-IREF)") (class "Default")
      (node (ref "R1") (pin "1") (pinfunction "1_1") (pintype "passive"))
      (node (ref "nrf1") (pin "16") (pinfunction "IREF_16") (pintype "passive"))
    )
    (net (code "58") (name "Net-(nrf1-VDD_PA)") (class "Default")
      (node (ref "C10") (pin "2") (pinfunction "2_2") (pintype "passive"))
      (node (ref "C11") (pin "2") (pinfunction "2_2") (pintype "passive"))
      (node (ref "L3") (pin "1") (pinfunction "1_1") (pintype "passive"))
      (node (ref "nrf1") (pin "11") (pinfunction "VDD_PA_11") (pintype "passive"))
    )
    (net (code "59") (name "Net-(nrf1-XC1)") (class "Default")
      (node (ref "C13") (pin "2") (pinfunction "2_2") (pintype "passive"))
      (node (ref "R8") (pin "2") (pinfunction "2_2") (pintype "passive"))
      (node (ref "XTAL1") (pin "1") (pinfunction "1_1") (pintype "passive"))
      (node (ref "nrf1") (pin "10") (pinfunction "XC1_10") (pintype "passive"))
    )
    (net (code "60") (name "Net-(nrf1-XC2)") (class "Default")
      (node (ref "C12") (pin "2") (pinfunction "2_2") (pintype "passive"))
      (node (ref "R8") (pin "1") (pinfunction "1_1") (pintype "passive"))
      (node (ref "XTAL1") (pin "3") (pinfunction "3_3") (pintype "passive"))
      (node (ref "nrf1") (pin "9") (pinfunction "XC2_9") (pintype "passive"))
    )
    (net (code "61") (name "VBAT") (class "Default")
      (node (ref "C18") (pin "2") (pinfunction "2_2") (pintype "passive"))
      (node (ref "D1") (pin "2") (pinfunction "K_2") (pintype "passive"))
      (node (ref "D2") (pin "2") (pinfunction "K_2") (pintype "passive"))
      (node (ref "D3") (pin "2") (pinfunction "K_2") (pintype "passive"))
      (node (ref "D4") (pin "2") (pinfunction "K_2") (pintype "passive"))
      (node (ref "Inductor1") (pin "1") (pinfunction "1_1") (pintype "passive"))
      (node (ref "M1") (pin "1") (pinfunction "1_1") (pintype "tri_state"))
      (node (ref "M2") (pin "1") (pinfunction "1_1") (pintype "tri_state"))
      (node (ref "M3") (pin "1") (pinfunction "1_1") (pintype "tri_state"))
      (node (ref "M4") (pin "1") (pinfunction "1_1") (pintype "tri_state"))
      (node (ref "R15") (pin "1") (pinfunction "1_1") (pintype "passive"))
      (node (ref "R2") (pin "2") (pinfunction "2_2") (pintype "passive"))
      (node (ref "SW-NO/OFF1") (pin "2") (pinfunction "2_2") (pintype "passive"))
      (node (ref "SX1") (pin "5") (pinfunction "IN_5") (pintype "passive"))
    )
    (net (code "62") (name "VBAT_IN") (class "Default")
      (node (ref "BAT1") (pin "1") (pinfunction "+_1") (pintype "passive"))
      (node (ref "SW-NO/OFF1") (pin "1") (pinfunction "1_1") (pintype "passive"))
    )
    (net (code "63") (name "unconnected-(MPU1-AUX_CL-Pad7)") (class "Default")
      (node (ref "MPU1") (pin "7") (pinfunction "AUX_CL_7") (pintype "passive"))
    )
    (net (code "64") (name "unconnected-(MPU1-AUX_DA-Pad6)") (class "Default")
      (node (ref "MPU1") (pin "6") (pinfunction "AUX_DA_6") (pintype "passive"))
    )
    (net (code "65") (name "unconnected-(MPU1-INT-Pad12)") (class "Default")
      (node (ref "MPU1") (pin "12") (pinfunction "INT_12") (pintype "passive"))
    )
    (net (code "66") (name "unconnected-(MPU1-NC-Pad2)") (class "Default")
      (node (ref "MPU1") (pin "2") (pinfunction "NC_2") (pintype "passive"))
    )
    (net (code "67") (name "unconnected-(MPU1-NC-Pad3)") (class "Default")
      (node (ref "MPU1") (pin "3") (pinfunction "NC_3") (pintype "passive"))
    )
    (net (code "68") (name "unconnected-(MPU1-NC-Pad4)") (class "Default")
      (node (ref "MPU1") (pin "4") (pinfunction "NC_4") (pintype "passive"))
    )
    (net (code "69") (name "unconnected-(MPU1-NC-Pad5)") (class "Default")
      (node (ref "MPU1") (pin "5") (pinfunction "NC_5") (pintype "passive"))
    )
    (net (code "70") (name "unconnected-(MPU1-NC-Pad14)") (class "Default")
      (node (ref "MPU1") (pin "14") (pinfunction "NC_14") (pintype "passive"))
    )
    (net (code "71") (name "unconnected-(MPU1-NC-Pad15)") (class "Default")
      (node (ref "MPU1") (pin "15") (pinfunction "NC_15") (pintype "passive"))
    )
    (net (code "72") (name "unconnected-(MPU1-NC-Pad16)") (class "Default")
      (node (ref "MPU1") (pin "16") (pinfunction "NC_16") (pintype "passive"))
    )
    (net (code "73") (name "unconnected-(MPU1-NC-Pad17)") (class "Default")
      (node (ref "MPU1") (pin "17") (pinfunction "NC_17") (pintype "passive"))
    )
    (net (code "74") (name "unconnected-(MPU1-RESV-Pad19)") (class "Default")
      (node (ref "MPU1") (pin "19") (pinfunction "RESV_19") (pintype "passive"))
    )
    (net (code "75") (name "unconnected-(MPU1-RESV-Pad21)") (class "Default")
      (node (ref "MPU1") (pin "21") (pinfunction "RESV_21") (pintype "passive"))
    )
    (net (code "76") (name "unconnected-(MPU1-RESV-Pad22)") (class "Default")
      (node (ref "MPU1") (pin "22") (pinfunction "RESV_22") (pintype "passive"))
    )
    (net (code "77") (name "unconnected-(SW-NO/OFF1-Pad3)") (class "Default")
      (node (ref "SW-NO/OFF1") (pin "3") (pinfunction "3_3") (pintype "passive"))
    )
    (net (code "78") (name "unconnected-(SX1-NC-Pad6)") (class "Default")
      (node (ref "SX1") (pin "6") (pinfunction "NC_6") (pintype "passive"))
    )
    (net (code "79") (name "unconnected-(U1-JNTRST{slash}PB4-Pad40)") (class "Default")
      (node (ref "U1") (pin "40") (pinfunction "JNTRST/PB4_40") (pintype "passive"))
    )
    (net (code "80") (name "unconnected-(U1-JTDI{slash}PA15-Pad38)") (class "Default")
      (node (ref "U1") (pin "38") (pinfunction "JTDI/PA15_38") (pintype "passive"))
    )
    (net (code "81") (name "unconnected-(U1-JTDO{slash}PB3-Pad39)") (class "Default")
      (node (ref "U1") (pin "39") (pinfunction "JTDO/PB3_39") (pintype "passive"))
    )
    (net (code "82") (name "unconnected-(U1-PA0{slash}ADC_IN0{slash}TIM2_CH1_ETR-Pad10)") (class "Default")
      (node (ref "U1") (pin "10") (pinfunction "PA0/ADC_IN0/TIM2_CH1_ETR_10") (pintype "passive"))
    )
    (net (code "83") (name "unconnected-(U1-PB5-Pad41)") (class "Default")
      (node (ref "U1") (pin "41") (pinfunction "PB5_41") (pintype "passive"))
    )
    (net (code "84") (name "unconnected-(nrf1-VDD-Pad18)") (class "Default")
      (node (ref "nrf1") (pin "18") (pinfunction "VDD_18") (pintype "passive"))
    )
  )
)
